# Steering.net
KiCad netlist of a schematic drawn in EAGLE
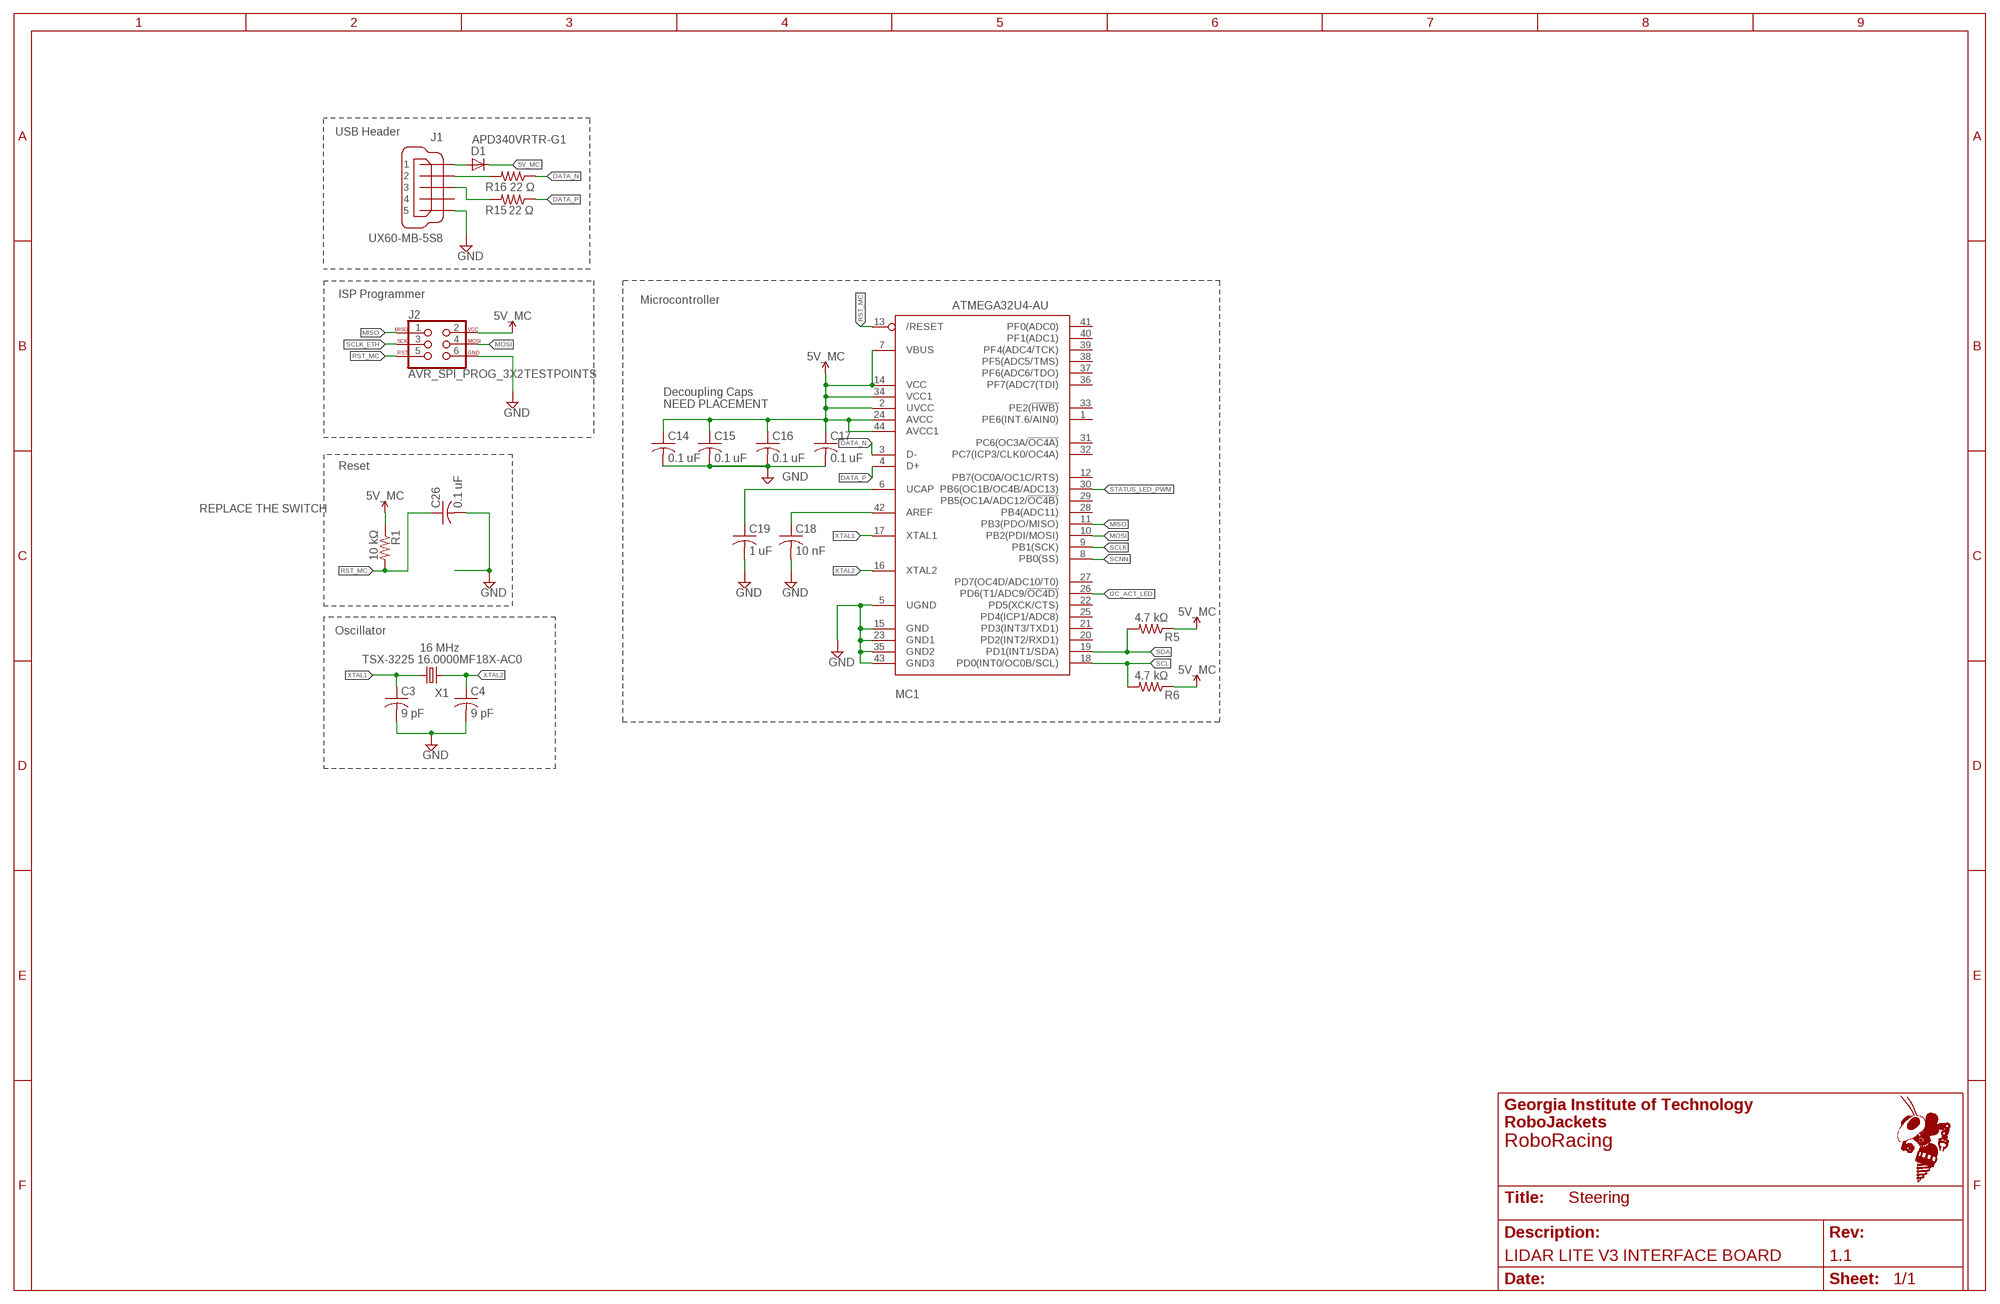
[diagram p0: schematic, sheet 1]

(export (version "E")
  (design (tool "Eeschema 10.0.6"))
  (components
    (comp (ref "C3")
      (value "9 pF")
      (footprint "eagle-import:C0603")
      (libsource (lib "eagle-import") (part "C-USC0603"))
    )
    (comp (ref "C4")
      (value "9 pF")
      (footprint "eagle-import:C0603")
      (libsource (lib "eagle-import") (part "C-USC0603"))
    )
    (comp (ref "C14")
      (value "0.1 uF")
      (footprint "eagle-import:C0603")
      (libsource (lib "eagle-import") (part "C-USC0603"))
    )
    (comp (ref "C15")
      (value "0.1 uF")
      (footprint "eagle-import:C0603")
      (libsource (lib "eagle-import") (part "C-USC0603"))
    )
    (comp (ref "C16")
      (value "0.1 uF")
      (footprint "eagle-import:C0603")
      (libsource (lib "eagle-import") (part "C-USC0603"))
    )
    (comp (ref "C17")
      (value "0.1 uF")
      (footprint "eagle-import:C0603")
      (libsource (lib "eagle-import") (part "C-USC0603"))
    )
    (comp (ref "C18")
      (value "10 nF")
      (footprint "eagle-import:C0603")
      (libsource (lib "eagle-import") (part "C-USC0603"))
    )
    (comp (ref "C19")
      (value "1 uF")
      (footprint "eagle-import:C0603")
      (libsource (lib "eagle-import") (part "C-USC0603"))
    )
    (comp (ref "C26")
      (value "0.1 uF")
      (footprint "eagle-import:C0603")
      (libsource (lib "eagle-import") (part "C-USC0603"))
    )
    (comp (ref "D1")
      (value "APD340VRTR-G1")
      (footprint "eagle-import:DO-214AC")
      (libsource (lib "eagle-import") (part "DIODE-DO-214AC"))
    )
    (comp (ref "J1")
      (value "UX60-MB-5S8")
      (footprint "eagle-import:UX60-MB-5S8")
      (libsource (lib "eagle-import") (part "UX60-MB-5S?8"))
    )
    (comp (ref "J2")
      (value "AVR_SPI_PROG_3X2TESTPOINTS")
      (footprint "eagle-import:2X3_TEST_POINTS")
      (libsource (lib "eagle-import") (part "AVR_SPI_PROG_3X2TESTPOINTS"))
    )
    (comp (ref "MC1")
      (value "ATMEGA32U4-AU")
      (footprint "eagle-import:TQFP44")
      (libsource (lib "eagle-import") (part "ATMEGA32U4-AU"))
    )
    (comp (ref "R1")
      (value "10 kΩ")
      (footprint "eagle-import:R0603")
      (libsource (lib "eagle-import") (part "R-US_R0603"))
    )
    (comp (ref "R5")
      (value "4.7 kΩ")
      (footprint "eagle-import:R0603")
      (libsource (lib "eagle-import") (part "R-US_R0603"))
    )
    (comp (ref "R6")
      (value "4.7 kΩ")
      (footprint "eagle-import:R0603")
      (libsource (lib "eagle-import") (part "R-US_R0603"))
    )
    (comp (ref "R15")
      (value "22 Ω")
      (footprint "eagle-import:R0603")
      (libsource (lib "eagle-import") (part "R-US_R0603"))
    )
    (comp (ref "R16")
      (value "22 Ω")
      (footprint "eagle-import:R0603")
      (libsource (lib "eagle-import") (part "R-US_R0603"))
    )
    (comp (ref "X1")
      (value "TSX-3225 16.0000MF18X-AC0")
      (footprint "eagle-import:XTAL-3.2X2.5")
      (libsource (lib "eagle-import") (part "XTAL-3.2X2.5"))
    )
  )
  (nets
    (net (code "1") (name "5V_MC") (class "Default")
      (node (ref "C14") (pin "1") (pinfunction "1_1") (pintype "passive"))
      (node (ref "C15") (pin "1") (pinfunction "1_1") (pintype "passive"))
      (node (ref "C16") (pin "1") (pinfunction "1_1") (pintype "passive"))
      (node (ref "C17") (pin "1") (pinfunction "1_1") (pintype "passive"))
      (node (ref "D1") (pin "C") (pinfunction "C_C") (pintype "passive"))
      (node (ref "J2") (pin "2") (pinfunction "2_2") (pintype "passive"))
      (node (ref "MC1") (pin "14") (pinfunction "VCC_14") (pintype "bidirectional"))
      (node (ref "MC1") (pin "2") (pinfunction "UVCC_2") (pintype "bidirectional"))
      (node (ref "MC1") (pin "24") (pinfunction "AVCC_24") (pintype "bidirectional"))
      (node (ref "MC1") (pin "34") (pinfunction "VCC1_34") (pintype "bidirectional"))
      (node (ref "MC1") (pin "44") (pinfunction "AVCC1_44") (pintype "bidirectional"))
      (node (ref "MC1") (pin "7") (pinfunction "VBUS_7") (pintype "bidirectional"))
      (node (ref "R1") (pin "1") (pinfunction "1_1") (pintype "passive"))
      (node (ref "R5") (pin "1") (pinfunction "1_1") (pintype "passive"))
      (node (ref "R6") (pin "1") (pinfunction "1_1") (pintype "passive"))
    )
    (net (code "2") (name "DATA_N") (class "Default")
      (node (ref "MC1") (pin "3") (pinfunction "D-_3") (pintype "bidirectional"))
      (node (ref "R16") (pin "1") (pinfunction "1_1") (pintype "passive"))
    )
    (net (code "3") (name "DATA_P") (class "Default")
      (node (ref "MC1") (pin "4") (pinfunction "D+_4") (pintype "bidirectional"))
      (node (ref "R15") (pin "1") (pinfunction "1_1") (pintype "passive"))
    )
    (net (code "4") (name "GND") (class "Default")
      (node (ref "C14") (pin "2") (pinfunction "2_2") (pintype "passive"))
      (node (ref "C15") (pin "2") (pinfunction "2_2") (pintype "passive"))
      (node (ref "C16") (pin "2") (pinfunction "2_2") (pintype "passive"))
      (node (ref "C17") (pin "2") (pinfunction "2_2") (pintype "passive"))
      (node (ref "C18") (pin "2") (pinfunction "2_2") (pintype "passive"))
      (node (ref "C19") (pin "2") (pinfunction "2_2") (pintype "passive"))
      (node (ref "C26") (pin "2") (pinfunction "2_2") (pintype "passive"))
      (node (ref "C3") (pin "2") (pinfunction "2_2") (pintype "passive"))
      (node (ref "C4") (pin "2") (pinfunction "2_2") (pintype "passive"))
      (node (ref "J1") (pin "5") (pinfunction "5_5") (pintype "passive"))
      (node (ref "J2") (pin "6") (pinfunction "6_6") (pintype "passive"))
      (node (ref "MC1") (pin "15") (pinfunction "GND_15") (pintype "bidirectional"))
      (node (ref "MC1") (pin "23") (pinfunction "GND1_23") (pintype "bidirectional"))
      (node (ref "MC1") (pin "35") (pinfunction "GND2_35") (pintype "bidirectional"))
      (node (ref "MC1") (pin "43") (pinfunction "GND3_43") (pintype "bidirectional"))
      (node (ref "MC1") (pin "5") (pinfunction "UGND_5") (pintype "bidirectional"))
    )
    (net (code "5") (name "I2C_ACT_LED") (class "Default")
      (node (ref "MC1") (pin "26") (pinfunction "PD6(T1/ADC9/~{OC4D})_26") (pintype "bidirectional"))
    )
    (net (code "6") (name "MISO") (class "Default")
      (node (ref "J2") (pin "1") (pinfunction "1_1") (pintype "passive"))
      (node (ref "MC1") (pin "11") (pinfunction "PB3(PDO/MISO)_11") (pintype "bidirectional"))
    )
    (net (code "7") (name "MOSI") (class "Default")
      (node (ref "J2") (pin "4") (pinfunction "4_4") (pintype "passive"))
      (node (ref "MC1") (pin "10") (pinfunction "PB2(PDI/MOSI)_10") (pintype "bidirectional"))
    )
    (net (code "8") (name "Net-(D1-PadA)") (class "Default")
      (node (ref "D1") (pin "A") (pinfunction "A_A") (pintype "passive"))
      (node (ref "J1") (pin "1") (pinfunction "1_1") (pintype "passive"))
    )
    (net (code "9") (name "Net-(J1-Pad2)") (class "Default")
      (node (ref "J1") (pin "2") (pinfunction "2_2") (pintype "passive"))
      (node (ref "R16") (pin "2") (pinfunction "2_2") (pintype "passive"))
    )
    (net (code "10") (name "Net-(J1-Pad3)") (class "Default")
      (node (ref "J1") (pin "3") (pinfunction "3_3") (pintype "passive"))
      (node (ref "R15") (pin "2") (pinfunction "2_2") (pintype "passive"))
    )
    (net (code "11") (name "Net-(MC1-AREF)") (class "Default")
      (node (ref "C18") (pin "1") (pinfunction "1_1") (pintype "passive"))
      (node (ref "MC1") (pin "42") (pinfunction "AREF_42") (pintype "bidirectional"))
    )
    (net (code "12") (name "Net-(MC1-UCAP)") (class "Default")
      (node (ref "C19") (pin "1") (pinfunction "1_1") (pintype "passive"))
      (node (ref "MC1") (pin "6") (pinfunction "UCAP_6") (pintype "bidirectional"))
    )
    (net (code "13") (name "RST_MC") (class "Default")
      (node (ref "C26") (pin "1") (pinfunction "1_1") (pintype "passive"))
      (node (ref "J2") (pin "5") (pinfunction "5_5") (pintype "passive"))
      (node (ref "MC1") (pin "13") (pinfunction "/RESET_13") (pintype "bidirectional"))
      (node (ref "R1") (pin "2") (pinfunction "2_2") (pintype "passive"))
    )
    (net (code "14") (name "SCL") (class "Default")
      (node (ref "MC1") (pin "18") (pinfunction "PD0(INT0/OC0B/SCL)_18") (pintype "bidirectional"))
      (node (ref "R6") (pin "2") (pinfunction "2_2") (pintype "passive"))
    )
    (net (code "15") (name "SCLK") (class "Default")
      (node (ref "MC1") (pin "9") (pinfunction "PB1(SCK)_9") (pintype "bidirectional"))
    )
    (net (code "16") (name "SCLK_ETH") (class "Default")
      (node (ref "J2") (pin "3") (pinfunction "3_3") (pintype "passive"))
    )
    (net (code "17") (name "SCNN") (class "Default")
      (node (ref "MC1") (pin "8") (pinfunction "PB0(SS)_8") (pintype "bidirectional"))
    )
    (net (code "18") (name "SDA") (class "Default")
      (node (ref "MC1") (pin "19") (pinfunction "PD1(INT1/SDA)_19") (pintype "bidirectional"))
      (node (ref "R5") (pin "2") (pinfunction "2_2") (pintype "passive"))
    )
    (net (code "19") (name "STATUS_LED_PWM") (class "Default")
      (node (ref "MC1") (pin "30") (pinfunction "PB6(OC1B/OC4B/ADC13)_30") (pintype "bidirectional"))
    )
    (net (code "20") (name "XTAL1") (class "Default")
      (node (ref "C3") (pin "1") (pinfunction "1_1") (pintype "passive"))
      (node (ref "MC1") (pin "17") (pinfunction "XTAL1_17") (pintype "bidirectional"))
      (node (ref "X1") (pin "1") (pinfunction "1_1") (pintype "passive"))
    )
    (net (code "21") (name "XTAL2") (class "Default")
      (node (ref "C4") (pin "1") (pinfunction "1_1") (pintype "passive"))
      (node (ref "MC1") (pin "16") (pinfunction "XTAL2_16") (pintype "bidirectional"))
      (node (ref "X1") (pin "3") (pinfunction "2_3") (pintype "passive"))
    )
    (net (code "22") (name "unconnected-(J1-Pad4)") (class "Default")
      (node (ref "J1") (pin "4") (pinfunction "4_4") (pintype "passive"))
    )
    (net (code "23") (name "unconnected-(MC1-PB4(ADC11)-Pad28)") (class "Default")
      (node (ref "MC1") (pin "28") (pinfunction "PB4(ADC11)_28") (pintype "bidirectional"))
    )
    (net (code "24") (name "unconnected-(MC1-PB5(OC1A{slash}ADC12{slash}~{OC4B})-Pad29)") (class "Default")
      (node (ref "MC1") (pin "29") (pinfunction "PB5(OC1A/ADC12/~{OC4B})_29") (pintype "bidirectional"))
    )
    (net (code "25") (name "unconnected-(MC1-PB7(OC0A{slash}OC1C{slash}RTS)-Pad12)") (class "Default")
      (node (ref "MC1") (pin "12") (pinfunction "PB7(OC0A/OC1C/RTS)_12") (pintype "bidirectional"))
    )
    (net (code "26") (name "unconnected-(MC1-PC6(OC3A{slash}~{OC4A})-Pad31)") (class "Default")
      (node (ref "MC1") (pin "31") (pinfunction "PC6(OC3A/~{OC4A})_31") (pintype "bidirectional"))
    )
    (net (code "27") (name "unconnected-(MC1-PC7(ICP3{slash}CLK0{slash}OC4A)-Pad32)") (class "Default")
      (node (ref "MC1") (pin "32") (pinfunction "PC7(ICP3/CLK0/OC4A)_32") (pintype "bidirectional"))
    )
    (net (code "28") (name "unconnected-(MC1-PD2(INT2{slash}RXD1)-Pad20)") (class "Default")
      (node (ref "MC1") (pin "20") (pinfunction "PD2(INT2/RXD1)_20") (pintype "bidirectional"))
    )
    (net (code "29") (name "unconnected-(MC1-PD3(INT3{slash}TXD1)-Pad21)") (class "Default")
      (node (ref "MC1") (pin "21") (pinfunction "PD3(INT3/TXD1)_21") (pintype "bidirectional"))
    )
    (net (code "30") (name "unconnected-(MC1-PD4(ICP1{slash}ADC8)-Pad25)") (class "Default")
      (node (ref "MC1") (pin "25") (pinfunction "PD4(ICP1/ADC8)_25") (pintype "bidirectional"))
    )
    (net (code "31") (name "unconnected-(MC1-PD5(XCK{slash}CTS)-Pad22)") (class "Default")
      (node (ref "MC1") (pin "22") (pinfunction "PD5(XCK/CTS)_22") (pintype "bidirectional"))
    )
    (net (code "32") (name "unconnected-(MC1-PD7(OC4D{slash}ADC10{slash}T0)-Pad27)") (class "Default")
      (node (ref "MC1") (pin "27") (pinfunction "PD7(OC4D/ADC10/T0)_27") (pintype "bidirectional"))
    )
    (net (code "33") (name "unconnected-(MC1-PE2(~{HWB})-Pad33)") (class "Default")
      (node (ref "MC1") (pin "33") (pinfunction "PE2(~{HWB})_33") (pintype "bidirectional"))
    )
    (net (code "34") (name "unconnected-(MC1-PE6(INT.6{slash}AIN0)-Pad1)") (class "Default")
      (node (ref "MC1") (pin "1") (pinfunction "PE6(INT.6/AIN0)_1") (pintype "bidirectional"))
    )
    (net (code "35") (name "unconnected-(MC1-PF0(ADC0)-Pad41)") (class "Default")
      (node (ref "MC1") (pin "41") (pinfunction "PF0(ADC0)_41") (pintype "bidirectional"))
    )
    (net (code "36") (name "unconnected-(MC1-PF1(ADC1)-Pad40)") (class "Default")
      (node (ref "MC1") (pin "40") (pinfunction "PF1(ADC1)_40") (pintype "bidirectional"))
    )
    (net (code "37") (name "unconnected-(MC1-PF4(ADC4{slash}TCK)-Pad39)") (class "Default")
      (node (ref "MC1") (pin "39") (pinfunction "PF4(ADC4/TCK)_39") (pintype "bidirectional"))
    )
    (net (code "38") (name "unconnected-(MC1-PF5(ADC5{slash}TMS)-Pad38)") (class "Default")
      (node (ref "MC1") (pin "38") (pinfunction "PF5(ADC5/TMS)_38") (pintype "bidirectional"))
    )
    (net (code "39") (name "unconnected-(MC1-PF6(ADC6{slash}TDO)-Pad37)") (class "Default")
      (node (ref "MC1") (pin "37") (pinfunction "PF6(ADC6/TDO)_37") (pintype "bidirectional"))
    )
    (net (code "40") (name "unconnected-(MC1-PF7(ADC7(TDI)-Pad36)") (class "Default")
      (node (ref "MC1") (pin "36") (pinfunction "PF7(ADC7(TDI)_36") (pintype "bidirectional"))
    )
  )
)
